# FMC_Clocks.net
KiCad netlist of a schematic drawn in Altium Designer
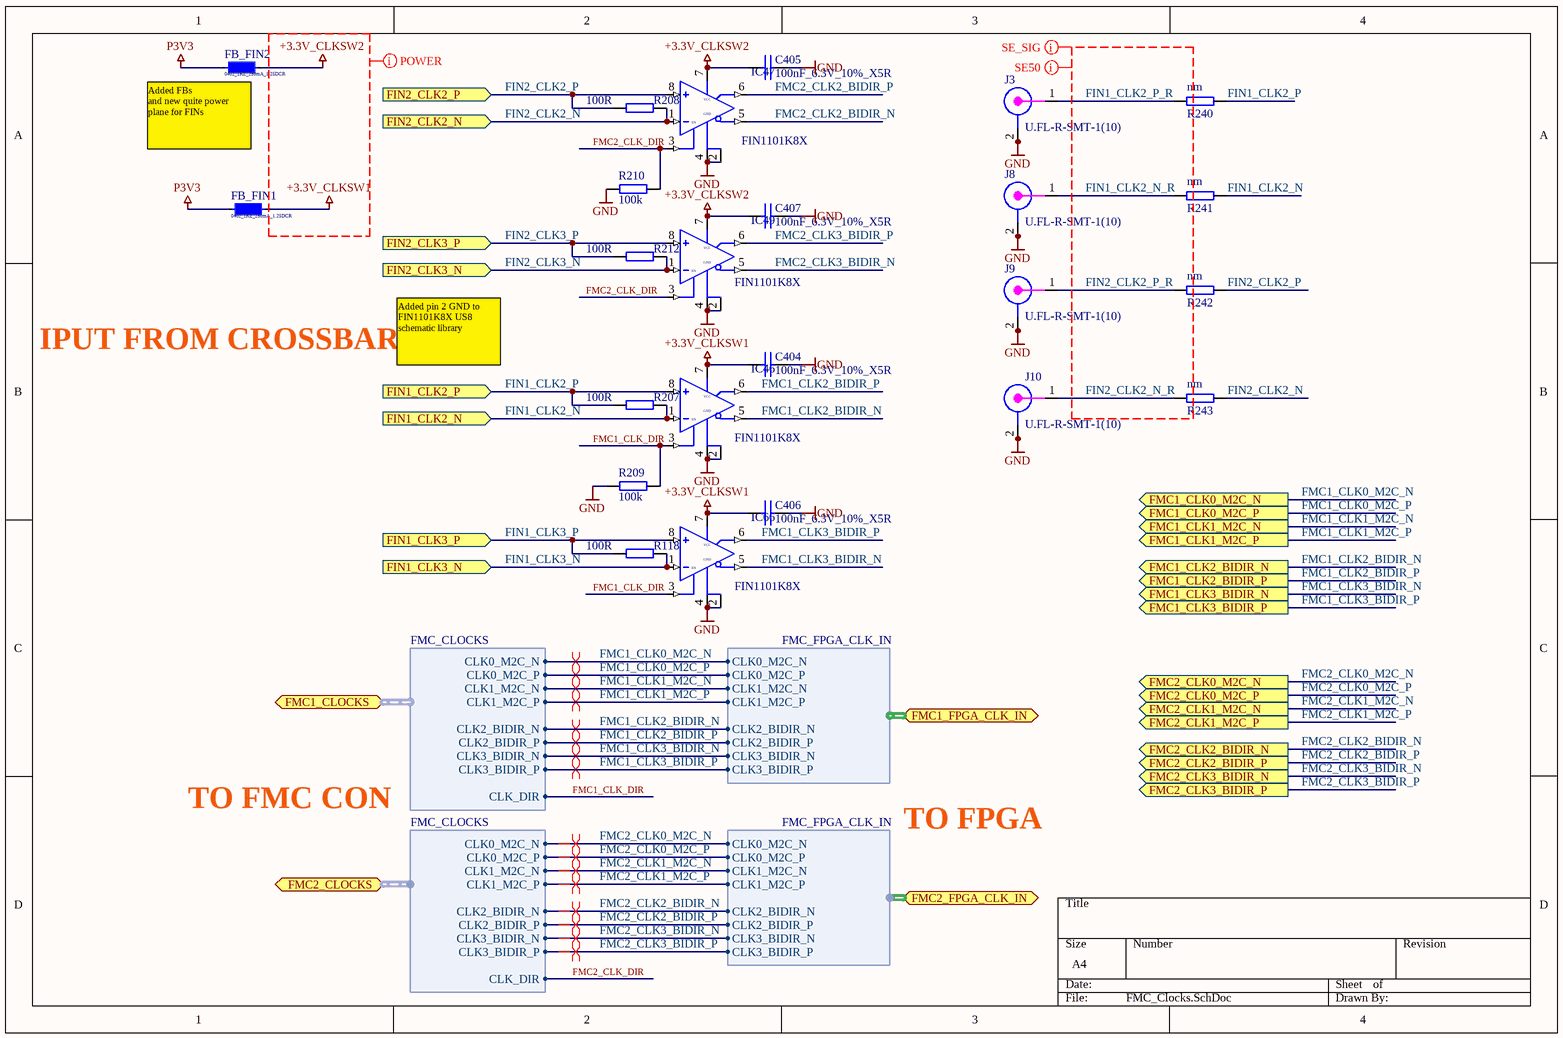
[diagram p0: FMC_Clocks.SchDoc]

(export (version "E")
  (design (tool "Eeschema 10.0.6"))
  (components
    (comp (ref "C404")
      (value "100nF_6.3V_10%_X5R")
      (footprint "0201C")
      (description "Capacitor SMD")
      (libsource (lib "LIBRARY_SCH") (part "CAP_SMD_0201"))
    )
    (comp (ref "C405")
      (value "100nF_6.3V_10%_X5R")
      (footprint "0201C")
      (description "Capacitor SMD")
      (libsource (lib "LIBRARY_SCH") (part "CAP_SMD_0201"))
    )
    (comp (ref "C406")
      (value "100nF_6.3V_10%_X5R")
      (footprint "0201C")
      (description "Capacitor SMD")
      (libsource (lib "LIBRARY_SCH") (part "CAP_SMD_0201"))
    )
    (comp (ref "C407")
      (value "100nF_6.3V_10%_X5R")
      (footprint "0201C")
      (description "Capacitor SMD")
      (libsource (lib "LIBRARY_SCH") (part "CAP_SMD_0201"))
    )
    (comp (ref "FB_FIN1")
      (value "0402_1KZ_250mA_1.25DCR")
      (footprint "INDC1005X55N")
      (description "FILTER CHIP 1000 OHM 250MA 0402")
      (fields
        (field (name "PART NUMBER") "BLM15HD102SN1D")
        (field (name "MANUFACTURER") "Murata Electronics North America")
      )
      (libsource (lib "Filters") (part "Ferrite Bead 2-pin"))
    )
    (comp (ref "FB_FIN2")
      (value "0402_1KZ_250mA_1.25DCR")
      (footprint "INDC1005X55N")
      (description "FILTER CHIP 1000 OHM 250MA 0402")
      (fields
        (field (name "PART NUMBER") "BLM15HD102SN1D")
        (field (name "MANUFACTURER") "Murata Electronics North America")
      )
      (libsource (lib "Filters") (part "Ferrite Bead 2-pin"))
    )
    (comp (ref "IC46")
      (value "FIN1101K8X")
      (footprint "US8")
      (description "LVDS TO LVDS repeater3.3V")
      (libsource (lib "AMC_FMC_Carrier") (part "IFC_FIN1101K8X"))
    )
    (comp (ref "IC47")
      (value "FIN1101K8X")
      (footprint "US8")
      (description "LVDS TO LVDS repeater3.3V")
      (libsource (lib "AMC_FMC_Carrier") (part "IFC_FIN1101K8X"))
    )
    (comp (ref "IC49")
      (value "FIN1101K8X")
      (footprint "US8")
      (description "LVDS TO LVDS repeater3.3V")
      (libsource (lib "AMC_FMC_Carrier") (part "IFC_FIN1101K8X"))
    )
    (comp (ref "IC66")
      (value "FIN1101K8X")
      (footprint "US8")
      (description "LVDS TO LVDS repeater3.3V")
      (libsource (lib "AMC_FMC_Carrier") (part "IFC_FIN1101K8X"))
    )
    (comp (ref "J3")
      (value "U.FL-R-SMT-1(10)")
      (footprint "CON_UFL_HIROSE_RECEPTACLE")
      (description "UFL")
      (libsource (lib "LIBRARY_SCH") (part "CON_UFL_SMD"))
    )
    (comp (ref "J8")
      (value "U.FL-R-SMT-1(10)")
      (footprint "CON_UFL_HIROSE_RECEPTACLE")
      (description "UFL")
      (libsource (lib "LIBRARY_SCH") (part "CON_UFL_SMD"))
    )
    (comp (ref "J9")
      (value "U.FL-R-SMT-1(10)")
      (footprint "CON_UFL_HIROSE_RECEPTACLE")
      (description "UFL")
      (libsource (lib "LIBRARY_SCH") (part "CON_UFL_SMD"))
    )
    (comp (ref "J10")
      (value "U.FL-R-SMT-1(10)")
      (footprint "CON_UFL_HIROSE_RECEPTACLE")
      (description "UFL")
      (libsource (lib "LIBRARY_SCH") (part "CON_UFL_SMD"))
    )
    (comp (ref "R118")
      (value "100R")
      (footprint "0402R")
      (description "SMD Resistor")
      (libsource (lib "LIBRARY_SCH") (part "RES_0402"))
    )
    (comp (ref "R207")
      (value "100R")
      (footprint "0402R")
      (description "SMD Resistor")
      (libsource (lib "LIBRARY_SCH") (part "RES_0402"))
    )
    (comp (ref "R208")
      (value "100R")
      (footprint "0402R")
      (description "SMD Resistor")
      (libsource (lib "LIBRARY_SCH") (part "RES_0402"))
    )
    (comp (ref "R209")
      (value "100k")
      (footprint "0402R")
      (description "SMD Resistor")
      (libsource (lib "LIBRARY_SCH") (part "RES_0402"))
    )
    (comp (ref "R210")
      (value "100k")
      (footprint "0402R")
      (description "SMD Resistor")
      (libsource (lib "LIBRARY_SCH") (part "RES_0402"))
    )
    (comp (ref "R212")
      (value "100R")
      (footprint "0402R")
      (description "SMD Resistor")
      (libsource (lib "LIBRARY_SCH") (part "RES_0402"))
    )
    (comp (ref "R240")
      (value "nm")
      (footprint "0402R")
      (description "SMD Resistor")
      (libsource (lib "LIBRARY_SCH") (part "RES_0402"))
    )
    (comp (ref "R241")
      (value "nm")
      (footprint "0402R")
      (description "SMD Resistor")
      (libsource (lib "LIBRARY_SCH") (part "RES_0402"))
    )
    (comp (ref "R242")
      (value "nm")
      (footprint "0402R")
      (description "SMD Resistor")
      (libsource (lib "LIBRARY_SCH") (part "RES_0402"))
    )
    (comp (ref "R243")
      (value "nm")
      (footprint "0402R")
      (description "SMD Resistor")
      (libsource (lib "LIBRARY_SCH") (part "RES_0402"))
    )
  )
  (nets
    (net (code "3") (name "+3.3V_CLKSW1") (class "Default")
      (node (ref "C404") (pin "1") (pinfunction "1_1") (pintype "passive"))
      (node (ref "C406") (pin "1") (pinfunction "1_1") (pintype "passive"))
      (node (ref "FB_FIN1") (pin "2") (pinfunction "-_2") (pintype "passive"))
      (node (ref "IC46") (pin "7") (pinfunction "VCC_7") (pintype "power_in"))
      (node (ref "IC66") (pin "7") (pinfunction "VCC_7") (pintype "power_in"))
    )
    (net (code "4") (name "+3.3V_CLKSW2") (class "Default")
      (node (ref "C405") (pin "1") (pinfunction "1_1") (pintype "passive"))
      (node (ref "C407") (pin "1") (pinfunction "1_1") (pintype "passive"))
      (node (ref "FB_FIN2") (pin "2") (pinfunction "-_2") (pintype "passive"))
      (node (ref "IC47") (pin "7") (pinfunction "VCC_7") (pintype "power_in"))
      (node (ref "IC49") (pin "7") (pinfunction "VCC_7") (pintype "power_in"))
    )
    (net (code "5") (name "/FIN1_CLK2_N") (class "Default")
      (node (ref "IC46") (pin "1") (pinfunction "IN_1") (pintype "input"))
      (node (ref "R207") (pin "1") (pinfunction "1_1") (pintype "passive"))
      (node (ref "R241") (pin "1") (pinfunction "1_1") (pintype "passive"))
    )
    (net (code "6") (name "/FIN1_CLK2_N_R") (class "Default")
      (node (ref "J8") (pin "1") (pintype "passive"))
      (node (ref "R241") (pin "2") (pinfunction "2_2") (pintype "passive"))
    )
    (net (code "7") (name "/FIN1_CLK2_P") (class "Default")
      (node (ref "IC46") (pin "8") (pinfunction "IN_8") (pintype "input"))
      (node (ref "R207") (pin "2") (pinfunction "2_2") (pintype "passive"))
      (node (ref "R240") (pin "1") (pinfunction "1_1") (pintype "passive"))
    )
    (net (code "8") (name "/FIN1_CLK2_P_R") (class "Default")
      (node (ref "J3") (pin "1") (pintype "passive"))
      (node (ref "R240") (pin "2") (pinfunction "2_2") (pintype "passive"))
    )
    (net (code "9") (name "/FIN1_CLK3_N") (class "Default")
      (node (ref "IC66") (pin "1") (pinfunction "IN_1") (pintype "input"))
      (node (ref "R118") (pin "1") (pinfunction "1_1") (pintype "passive"))
    )
    (net (code "10") (name "/FIN1_CLK3_P") (class "Default")
      (node (ref "IC66") (pin "8") (pinfunction "IN_8") (pintype "input"))
      (node (ref "R118") (pin "2") (pinfunction "2_2") (pintype "passive"))
    )
    (net (code "11") (name "/FIN2_CLK2_N") (class "Default")
      (node (ref "IC47") (pin "1") (pinfunction "IN_1") (pintype "input"))
      (node (ref "R208") (pin "1") (pinfunction "1_1") (pintype "passive"))
      (node (ref "R243") (pin "1") (pinfunction "1_1") (pintype "passive"))
    )
    (net (code "12") (name "/FIN2_CLK2_N_R") (class "Default")
      (node (ref "J10") (pin "1") (pintype "passive"))
      (node (ref "R243") (pin "2") (pinfunction "2_2") (pintype "passive"))
    )
    (net (code "13") (name "/FIN2_CLK2_P") (class "Default")
      (node (ref "IC47") (pin "8") (pinfunction "IN_8") (pintype "input"))
      (node (ref "R208") (pin "2") (pinfunction "2_2") (pintype "passive"))
      (node (ref "R242") (pin "1") (pinfunction "1_1") (pintype "passive"))
    )
    (net (code "14") (name "/FIN2_CLK2_P_R") (class "Default")
      (node (ref "J9") (pin "1") (pintype "passive"))
      (node (ref "R242") (pin "2") (pinfunction "2_2") (pintype "passive"))
    )
    (net (code "15") (name "/FIN2_CLK3_N") (class "Default")
      (node (ref "IC49") (pin "1") (pinfunction "IN_1") (pintype "input"))
      (node (ref "R212") (pin "1") (pinfunction "1_1") (pintype "passive"))
    )
    (net (code "16") (name "/FIN2_CLK3_P") (class "Default")
      (node (ref "IC49") (pin "8") (pinfunction "IN_8") (pintype "input"))
      (node (ref "R212") (pin "2") (pinfunction "2_2") (pintype "passive"))
    )
    (net (code "21") (name "/FMC1_CLK2_BIDIR_N") (class "Default")
      (node (ref "IC46") (pin "5") (pinfunction "~{Q}_5") (pintype "output"))
    )
    (net (code "22") (name "/FMC1_CLK2_BIDIR_P") (class "Default")
      (node (ref "IC46") (pin "6") (pinfunction "Q_6") (pintype "output"))
    )
    (net (code "23") (name "/FMC1_CLK3_BIDIR_N") (class "Default")
      (node (ref "IC66") (pin "5") (pinfunction "~{Q}_5") (pintype "output"))
    )
    (net (code "24") (name "/FMC1_CLK3_BIDIR_P") (class "Default")
      (node (ref "IC66") (pin "6") (pinfunction "Q_6") (pintype "output"))
    )
    (net (code "25") (name "/FMC1_CLK_DIR") (class "Default")
      (node (ref "IC46") (pin "3") (pinfunction "EN_3") (pintype "input"))
      (node (ref "IC66") (pin "3") (pinfunction "EN_3") (pintype "input"))
      (node (ref "R209") (pin "2") (pinfunction "2_2") (pintype "passive"))
    )
    (net (code "30") (name "/FMC2_CLK2_BIDIR_N") (class "Default")
      (node (ref "IC47") (pin "5") (pinfunction "~{Q}_5") (pintype "output"))
    )
    (net (code "31") (name "/FMC2_CLK2_BIDIR_P") (class "Default")
      (node (ref "IC47") (pin "6") (pinfunction "Q_6") (pintype "output"))
    )
    (net (code "32") (name "/FMC2_CLK3_BIDIR_N") (class "Default")
      (node (ref "IC49") (pin "5") (pinfunction "~{Q}_5") (pintype "output"))
    )
    (net (code "33") (name "/FMC2_CLK3_BIDIR_P") (class "Default")
      (node (ref "IC49") (pin "6") (pinfunction "Q_6") (pintype "output"))
    )
    (net (code "34") (name "/FMC2_CLK_DIR") (class "Default")
      (node (ref "IC47") (pin "3") (pinfunction "EN_3") (pintype "input"))
      (node (ref "IC49") (pin "3") (pinfunction "EN_3") (pintype "input"))
      (node (ref "R210") (pin "2") (pinfunction "2_2") (pintype "passive"))
    )
    (net (code "37") (name "GND") (class "Default")
      (node (ref "C404") (pin "2") (pinfunction "2_2") (pintype "passive"))
      (node (ref "C405") (pin "2") (pinfunction "2_2") (pintype "passive"))
      (node (ref "C406") (pin "2") (pinfunction "2_2") (pintype "passive"))
      (node (ref "C407") (pin "2") (pinfunction "2_2") (pintype "passive"))
      (node (ref "IC46") (pin "2") (pinfunction "GND_2") (pintype "power_in"))
      (node (ref "IC46") (pin "4") (pinfunction "GND_4") (pintype "power_in"))
      (node (ref "IC47") (pin "2") (pinfunction "GND_2") (pintype "power_in"))
      (node (ref "IC47") (pin "4") (pinfunction "GND_4") (pintype "power_in"))
      (node (ref "IC49") (pin "2") (pinfunction "GND_2") (pintype "power_in"))
      (node (ref "IC49") (pin "4") (pinfunction "GND_4") (pintype "power_in"))
      (node (ref "IC66") (pin "2") (pinfunction "GND_2") (pintype "power_in"))
      (node (ref "IC66") (pin "4") (pinfunction "GND_4") (pintype "power_in"))
      (node (ref "J10") (pin "2") (pintype "passive"))
      (node (ref "J10") (pin "2a") (pinfunction "GND_2a") (pintype "passive"))
      (node (ref "J3") (pin "2") (pintype "passive"))
      (node (ref "J3") (pin "2a") (pinfunction "GND_2a") (pintype "passive"))
      (node (ref "J8") (pin "2") (pintype "passive"))
      (node (ref "J8") (pin "2a") (pinfunction "GND_2a") (pintype "passive"))
      (node (ref "J9") (pin "2") (pintype "passive"))
      (node (ref "J9") (pin "2a") (pinfunction "GND_2a") (pintype "passive"))
      (node (ref "R209") (pin "1") (pinfunction "1_1") (pintype "passive"))
      (node (ref "R210") (pin "1") (pinfunction "1_1") (pintype "passive"))
    )
    (net (code "38") (name "P3V3") (class "Default")
      (node (ref "FB_FIN1") (pin "1") (pinfunction "+_1") (pintype "passive"))
      (node (ref "FB_FIN2") (pin "1") (pinfunction "+_1") (pintype "passive"))
    )
  )
)
